# ERobot_Minimalis_-_2023.net
KiCad netlist of a schematic drawn in EAGLE
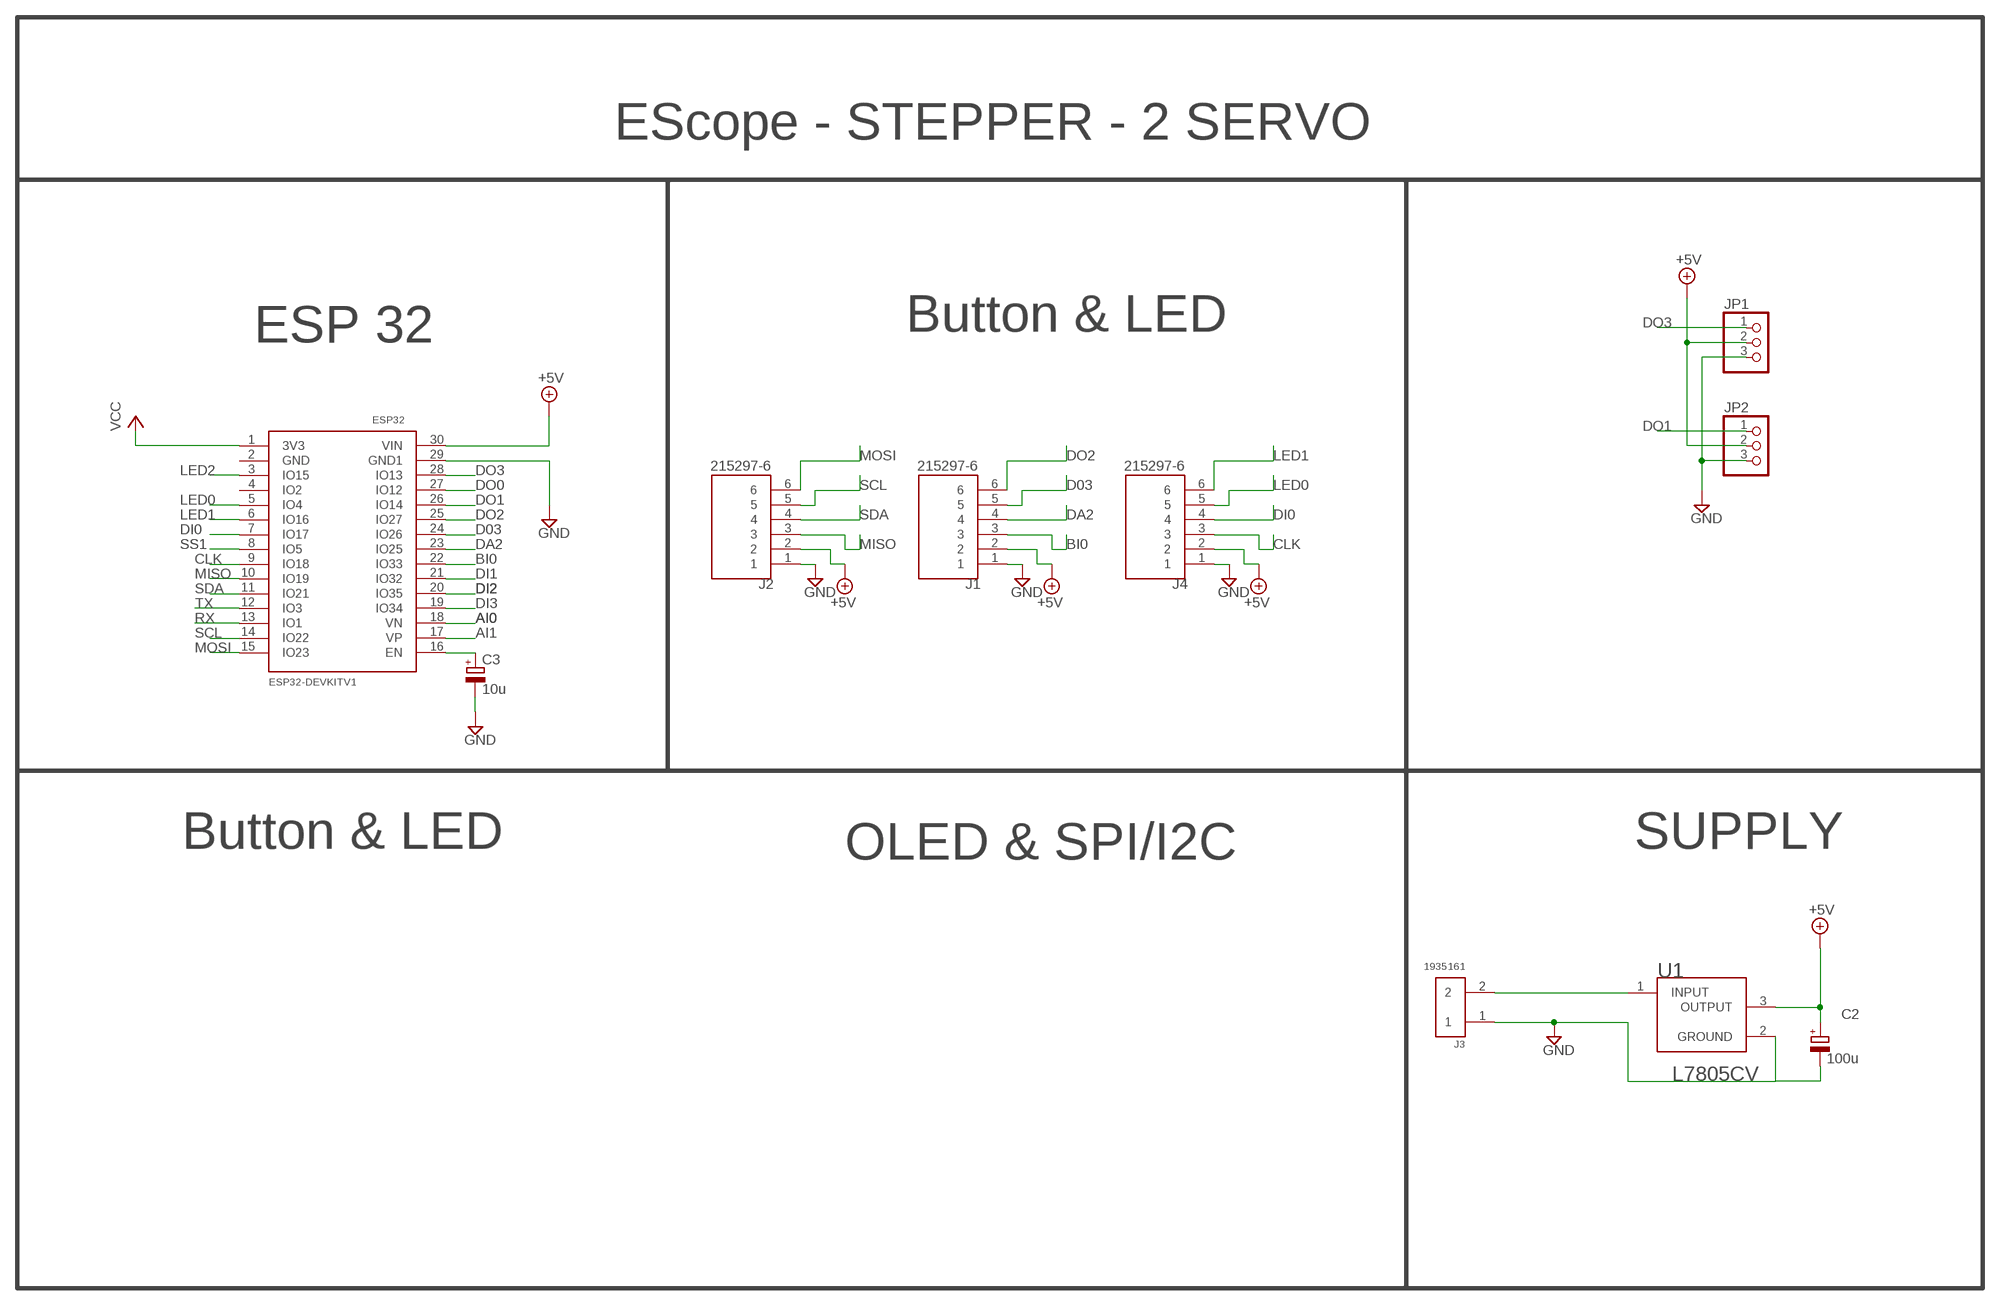
[diagram p0: schematic, sheet 1]

(export (version "E")
  (design (tool "Eeschema 10.0.6"))
  (components
    (comp (ref "C2")
      (value "100u")
      (footprint "eagle-import:E3,5-8")
      (libsource (lib "eagle-import") (part "CPOL-EUE3.5-8"))
    )
    (comp (ref "C3")
      (value "10u")
      (footprint "eagle-import:E2,5-5")
      (libsource (lib "eagle-import") (part "CPOL-EUE2.5-5"))
    )
    (comp (ref "ESP32")
      (value "DEVKIT-V1")
      (footprint "eagle-import:ESP32-DEVKITV1")
      (libsource (lib "eagle-import") (part "ESP32DEVKITV1"))
    )
    (comp (ref "J1")
      (value "215297-6")
      (footprint "eagle-import:TE_215297-6")
      (fields (field (name "MF") "TE Connectivity"))
      (libsource (lib "eagle-import") (part "215297-6"))
    )
    (comp (ref "J2")
      (value "215297-6")
      (footprint "eagle-import:TE_215297-6")
      (fields (field (name "MF") "TE Connectivity"))
      (libsource (lib "eagle-import") (part "215297-6"))
    )
    (comp (ref "J3")
      (value "1935161")
      (footprint "eagle-import:PHOENIX_1935161")
      (fields (field (name "MF") "Phoenix Contact"))
      (libsource (lib "eagle-import") (part "1935161"))
    )
    (comp (ref "J4")
      (value "215297-6")
      (footprint "eagle-import:TE_215297-6")
      (fields (field (name "MF") "TE Connectivity"))
      (libsource (lib "eagle-import") (part "215297-6"))
    )
    (comp (ref "JP1")
      (value "PINHD-1X3")
      (footprint "eagle-import:1X03")
      (libsource (lib "eagle-import") (part "PINHD-1X3"))
    )
    (comp (ref "JP2")
      (value "PINHD-1X3")
      (footprint "eagle-import:1X03")
      (libsource (lib "eagle-import") (part "PINHD-1X3"))
    )
    (comp (ref "U1")
      (value "STMICROELECTRONICS_L7805CVSTMICROELECTRONICS_L7805CV_0_0")
      (footprint "eagle-import:STMICROELECTRONICS_L7805CV_0")
      (fields
        (field (name "DIGIKEY_PART_NUMBER") "497-1443-5-ND")
        (field (name "MF") "STMicroelectronics")
        (field (name "MOUSER_PART_NUMBER") "511-L7805CV")
      )
      (libsource (lib "eagle-import") (part "STMICROELECTRONICS_L7805CVSTMICROELECTRONICS_L7805CV_0_0"))
    )
  )
  (nets
    (net (code "1") (name "+5V") (class "Default")
      (node (ref "C2") (pin "+") (pinfunction "+_+") (pintype "passive"))
      (node (ref "ESP32") (pin "30") (pinfunction "VIN_30") (pintype "bidirectional"))
      (node (ref "J1") (pin "2") (pinfunction "2_2") (pintype "passive"))
      (node (ref "J2") (pin "2") (pinfunction "2_2") (pintype "passive"))
      (node (ref "J4") (pin "2") (pinfunction "2_2") (pintype "passive"))
      (node (ref "JP1") (pin "2") (pinfunction "2_2") (pintype "passive"))
      (node (ref "JP2") (pin "2") (pinfunction "2_2") (pintype "passive"))
      (node (ref "U1") (pin "3") (pinfunction "OUTPUT_3") (pintype "bidirectional"))
    )
    (net (code "2") (name "/AI0") (class "Default")
      (node (ref "ESP32") (pin "18") (pinfunction "VN_18") (pintype "bidirectional"))
    )
    (net (code "3") (name "/AI1") (class "Default")
      (node (ref "ESP32") (pin "17") (pinfunction "VP_17") (pintype "bidirectional"))
    )
    (net (code "4") (name "/BI0") (class "Default")
      (node (ref "ESP32") (pin "22") (pinfunction "IO33_22") (pintype "bidirectional"))
      (node (ref "J1") (pin "3") (pinfunction "3_3") (pintype "passive"))
    )
    (net (code "5") (name "/CLK") (class "Default")
      (node (ref "ESP32") (pin "9") (pinfunction "IO18_9") (pintype "bidirectional"))
      (node (ref "J4") (pin "3") (pinfunction "3_3") (pintype "passive"))
    )
    (net (code "6") (name "/D03") (class "Default")
      (node (ref "ESP32") (pin "24") (pinfunction "IO26_24") (pintype "bidirectional"))
      (node (ref "J1") (pin "5") (pinfunction "5_5") (pintype "passive"))
    )
    (net (code "7") (name "/DA2") (class "Default")
      (node (ref "ESP32") (pin "23") (pinfunction "IO25_23") (pintype "bidirectional"))
      (node (ref "J1") (pin "4") (pinfunction "4_4") (pintype "passive"))
    )
    (net (code "8") (name "/DI0") (class "Default")
      (node (ref "ESP32") (pin "7") (pinfunction "IO17_7") (pintype "bidirectional"))
      (node (ref "J4") (pin "4") (pinfunction "4_4") (pintype "passive"))
    )
    (net (code "9") (name "/DI1") (class "Default")
      (node (ref "ESP32") (pin "21") (pinfunction "IO32_21") (pintype "bidirectional"))
    )
    (net (code "10") (name "/DI2") (class "Default")
      (node (ref "ESP32") (pin "20") (pinfunction "IO35_20") (pintype "bidirectional"))
    )
    (net (code "11") (name "/DI3") (class "Default")
      (node (ref "ESP32") (pin "19") (pinfunction "IO34_19") (pintype "bidirectional"))
    )
    (net (code "12") (name "/DO0") (class "Default")
      (node (ref "ESP32") (pin "27") (pinfunction "IO12_27") (pintype "bidirectional"))
    )
    (net (code "13") (name "/DO1") (class "Default")
      (node (ref "ESP32") (pin "26") (pinfunction "IO14_26") (pintype "bidirectional"))
      (node (ref "JP2") (pin "1") (pinfunction "1_1") (pintype "passive"))
    )
    (net (code "14") (name "/DO2") (class "Default")
      (node (ref "ESP32") (pin "25") (pinfunction "IO27_25") (pintype "bidirectional"))
      (node (ref "J1") (pin "6") (pinfunction "6_6") (pintype "passive"))
    )
    (net (code "15") (name "/DO3") (class "Default")
      (node (ref "ESP32") (pin "28") (pinfunction "IO13_28") (pintype "bidirectional"))
      (node (ref "JP1") (pin "1") (pinfunction "1_1") (pintype "passive"))
    )
    (net (code "16") (name "/LED0") (class "Default")
      (node (ref "ESP32") (pin "5") (pinfunction "IO4_5") (pintype "bidirectional"))
      (node (ref "J4") (pin "5") (pinfunction "5_5") (pintype "passive"))
    )
    (net (code "17") (name "/LED1") (class "Default")
      (node (ref "ESP32") (pin "6") (pinfunction "IO16_6") (pintype "bidirectional"))
      (node (ref "J4") (pin "6") (pinfunction "6_6") (pintype "passive"))
    )
    (net (code "18") (name "/LED2") (class "Default")
      (node (ref "ESP32") (pin "3") (pinfunction "IO15_3") (pintype "bidirectional"))
    )
    (net (code "19") (name "/MISO") (class "Default")
      (node (ref "ESP32") (pin "10") (pinfunction "IO19_10") (pintype "bidirectional"))
      (node (ref "J2") (pin "3") (pinfunction "3_3") (pintype "passive"))
    )
    (net (code "20") (name "/MOSI") (class "Default")
      (node (ref "ESP32") (pin "15") (pinfunction "IO23_15") (pintype "bidirectional"))
      (node (ref "J2") (pin "6") (pinfunction "6_6") (pintype "passive"))
    )
    (net (code "21") (name "/RX") (class "Default")
      (node (ref "ESP32") (pin "13") (pinfunction "IO1_13") (pintype "bidirectional"))
    )
    (net (code "22") (name "/SCL") (class "Default")
      (node (ref "ESP32") (pin "14") (pinfunction "IO22_14") (pintype "bidirectional"))
      (node (ref "J2") (pin "5") (pinfunction "5_5") (pintype "passive"))
    )
    (net (code "23") (name "/SDA") (class "Default")
      (node (ref "ESP32") (pin "11") (pinfunction "IO21_11") (pintype "bidirectional"))
      (node (ref "J2") (pin "4") (pinfunction "4_4") (pintype "passive"))
    )
    (net (code "24") (name "/SS1") (class "Default")
      (node (ref "ESP32") (pin "8") (pinfunction "IO5_8") (pintype "bidirectional"))
    )
    (net (code "25") (name "/TX") (class "Default")
      (node (ref "ESP32") (pin "12") (pinfunction "IO3_12") (pintype "bidirectional"))
    )
    (net (code "26") (name "GND") (class "Default")
      (node (ref "C2") (pin "-") (pinfunction "-_-") (pintype "passive"))
      (node (ref "C3") (pin "-") (pinfunction "-_-") (pintype "passive"))
      (node (ref "ESP32") (pin "29") (pinfunction "GND1_29") (pintype "bidirectional"))
      (node (ref "J1") (pin "1") (pinfunction "1_1") (pintype "passive"))
      (node (ref "J2") (pin "1") (pinfunction "1_1") (pintype "passive"))
      (node (ref "J3") (pin "1") (pinfunction "1_1") (pintype "passive"))
      (node (ref "J4") (pin "1") (pinfunction "1_1") (pintype "passive"))
      (node (ref "JP1") (pin "3") (pinfunction "3_3") (pintype "passive"))
      (node (ref "JP2") (pin "3") (pinfunction "3_3") (pintype "passive"))
      (node (ref "U1") (pin "2") (pinfunction "GROUND_2") (pintype "bidirectional"))
    )
    (net (code "27") (name "Net-(ESP32-EN)") (class "Default")
      (node (ref "C3") (pin "+") (pinfunction "+_+") (pintype "passive"))
      (node (ref "ESP32") (pin "16") (pinfunction "EN_16") (pintype "bidirectional"))
    )
    (net (code "28") (name "Net-(U1-INPUT)") (class "Default")
      (node (ref "J3") (pin "2") (pinfunction "2_2") (pintype "passive"))
      (node (ref "U1") (pin "1") (pinfunction "INPUT_1") (pintype "bidirectional"))
    )
    (net (code "29") (name "VCC") (class "Default")
      (node (ref "ESP32") (pin "1") (pinfunction "3V3_1") (pintype "bidirectional"))
    )
    (net (code "30") (name "unconnected-(ESP32-GND-Pad2)") (class "Default")
      (node (ref "ESP32") (pin "2") (pinfunction "GND_2") (pintype "bidirectional"))
    )
    (net (code "31") (name "unconnected-(ESP32-IO2-Pad4)") (class "Default")
      (node (ref "ESP32") (pin "4") (pinfunction "IO2_4") (pintype "bidirectional"))
    )
  )
)
